# astable.net
KiCad netlist of a schematic drawn in EAGLE
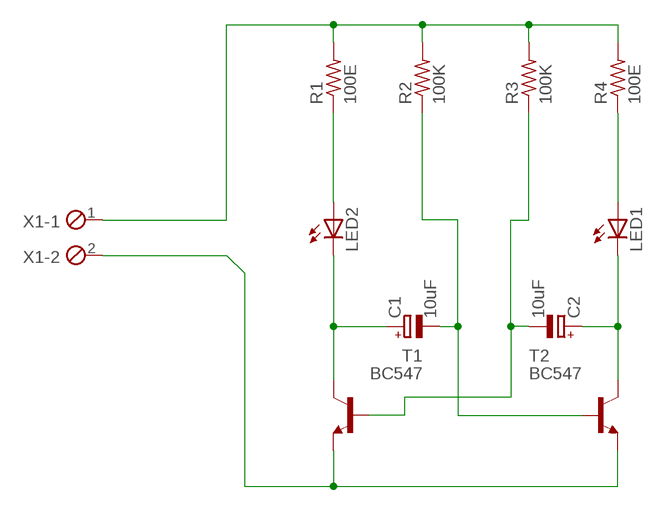
[diagram p0: schematic, sheet 1]

(export (version "E")
  (design (tool "Eeschema 10.0.6"))
  (components
    (comp (ref "C1")
      (value "10uF")
      (footprint "eagle-import:E2,5-6")
      (libsource (lib "eagle-import") (part "CPOL-EUE2.5-6"))
    )
    (comp (ref "C2")
      (value "10uF")
      (footprint "eagle-import:E2,5-6")
      (libsource (lib "eagle-import") (part "CPOL-EUE2.5-6"))
    )
    (comp (ref "LED1")
      (value "LED5MM")
      (footprint "eagle-import:LED5MM")
      (libsource (lib "eagle-import") (part "LED5MM"))
    )
    (comp (ref "LED2")
      (value "LED5MM")
      (footprint "eagle-import:LED5MM")
      (libsource (lib "eagle-import") (part "LED5MM"))
    )
    (comp (ref "R1")
      (value "100E")
      (footprint "eagle-import:0207_7")
      (libsource (lib "eagle-import") (part "R-US_0207/7"))
    )
    (comp (ref "R2")
      (value "100K")
      (footprint "eagle-import:0207_7")
      (libsource (lib "eagle-import") (part "R-US_0207/7"))
    )
    (comp (ref "R3")
      (value "100K")
      (footprint "eagle-import:0207_7")
      (libsource (lib "eagle-import") (part "R-US_0207/7"))
    )
    (comp (ref "R4")
      (value "100E")
      (footprint "eagle-import:0207_7")
      (libsource (lib "eagle-import") (part "R-US_0207/7"))
    )
    (comp (ref "T1")
      (value "BC547")
      (footprint "eagle-import:TO92")
      (libsource (lib "eagle-import") (part "BC547"))
    )
    (comp (ref "T2")
      (value "BC547")
      (footprint "eagle-import:TO92")
      (libsource (lib "eagle-import") (part "BC547"))
    )
    (comp (ref "X1")
      (value "MPT2")
      (footprint "eagle-import:2POL254")
      (libsource (lib "eagle-import") (part "MPT2"))
    )
  )
  (nets
    (net (code "1") (name "Net-(LED1-C)") (class "Default")
      (node (ref "C2") (pin "+") (pinfunction "+_+") (pintype "passive"))
      (node (ref "LED1") (pin "K") (pinfunction "C_K") (pintype "passive"))
      (node (ref "T2") (pin "3") (pinfunction "C_3") (pintype "passive"))
    )
    (net (code "2") (name "Net-(LED1-PadA)") (class "Default")
      (node (ref "LED1") (pin "A") (pinfunction "A_A") (pintype "passive"))
      (node (ref "R4") (pin "1") (pinfunction "1_1") (pintype "passive"))
    )
    (net (code "3") (name "Net-(LED2-C)") (class "Default")
      (node (ref "C1") (pin "+") (pinfunction "+_+") (pintype "passive"))
      (node (ref "LED2") (pin "K") (pinfunction "C_K") (pintype "passive"))
      (node (ref "T1") (pin "3") (pinfunction "C_3") (pintype "passive"))
    )
    (net (code "4") (name "Net-(LED2-PadA)") (class "Default")
      (node (ref "LED2") (pin "A") (pinfunction "A_A") (pintype "passive"))
      (node (ref "R1") (pin "1") (pinfunction "1_1") (pintype "passive"))
    )
    (net (code "5") (name "Net-(R1-Pad2)") (class "Default")
      (node (ref "R1") (pin "2") (pinfunction "2_2") (pintype "passive"))
      (node (ref "R2") (pin "2") (pinfunction "2_2") (pintype "passive"))
      (node (ref "R3") (pin "2") (pinfunction "2_2") (pintype "passive"))
      (node (ref "R4") (pin "2") (pinfunction "2_2") (pintype "passive"))
      (node (ref "X1") (pin "1") (pinfunction "1_1") (pintype "passive"))
    )
    (net (code "6") (name "Net-(T1-B)") (class "Default")
      (node (ref "C2") (pin "-") (pinfunction "-_-") (pintype "passive"))
      (node (ref "R3") (pin "1") (pinfunction "1_1") (pintype "passive"))
      (node (ref "T1") (pin "2") (pinfunction "B_2") (pintype "passive"))
    )
    (net (code "7") (name "Net-(T1-E)") (class "Default")
      (node (ref "T1") (pin "1") (pinfunction "E_1") (pintype "passive"))
      (node (ref "T2") (pin "1") (pinfunction "E_1") (pintype "passive"))
      (node (ref "X1") (pin "2") (pinfunction "1_2") (pintype "passive"))
    )
    (net (code "8") (name "Net-(T2-B)") (class "Default")
      (node (ref "C1") (pin "-") (pinfunction "-_-") (pintype "passive"))
      (node (ref "R2") (pin "1") (pinfunction "1_1") (pintype "passive"))
      (node (ref "T2") (pin "2") (pinfunction "B_2") (pintype "passive"))
    )
  )
)
